# ModelP_ytki.net
KiCad netlist of a schematic drawn in EAGLE
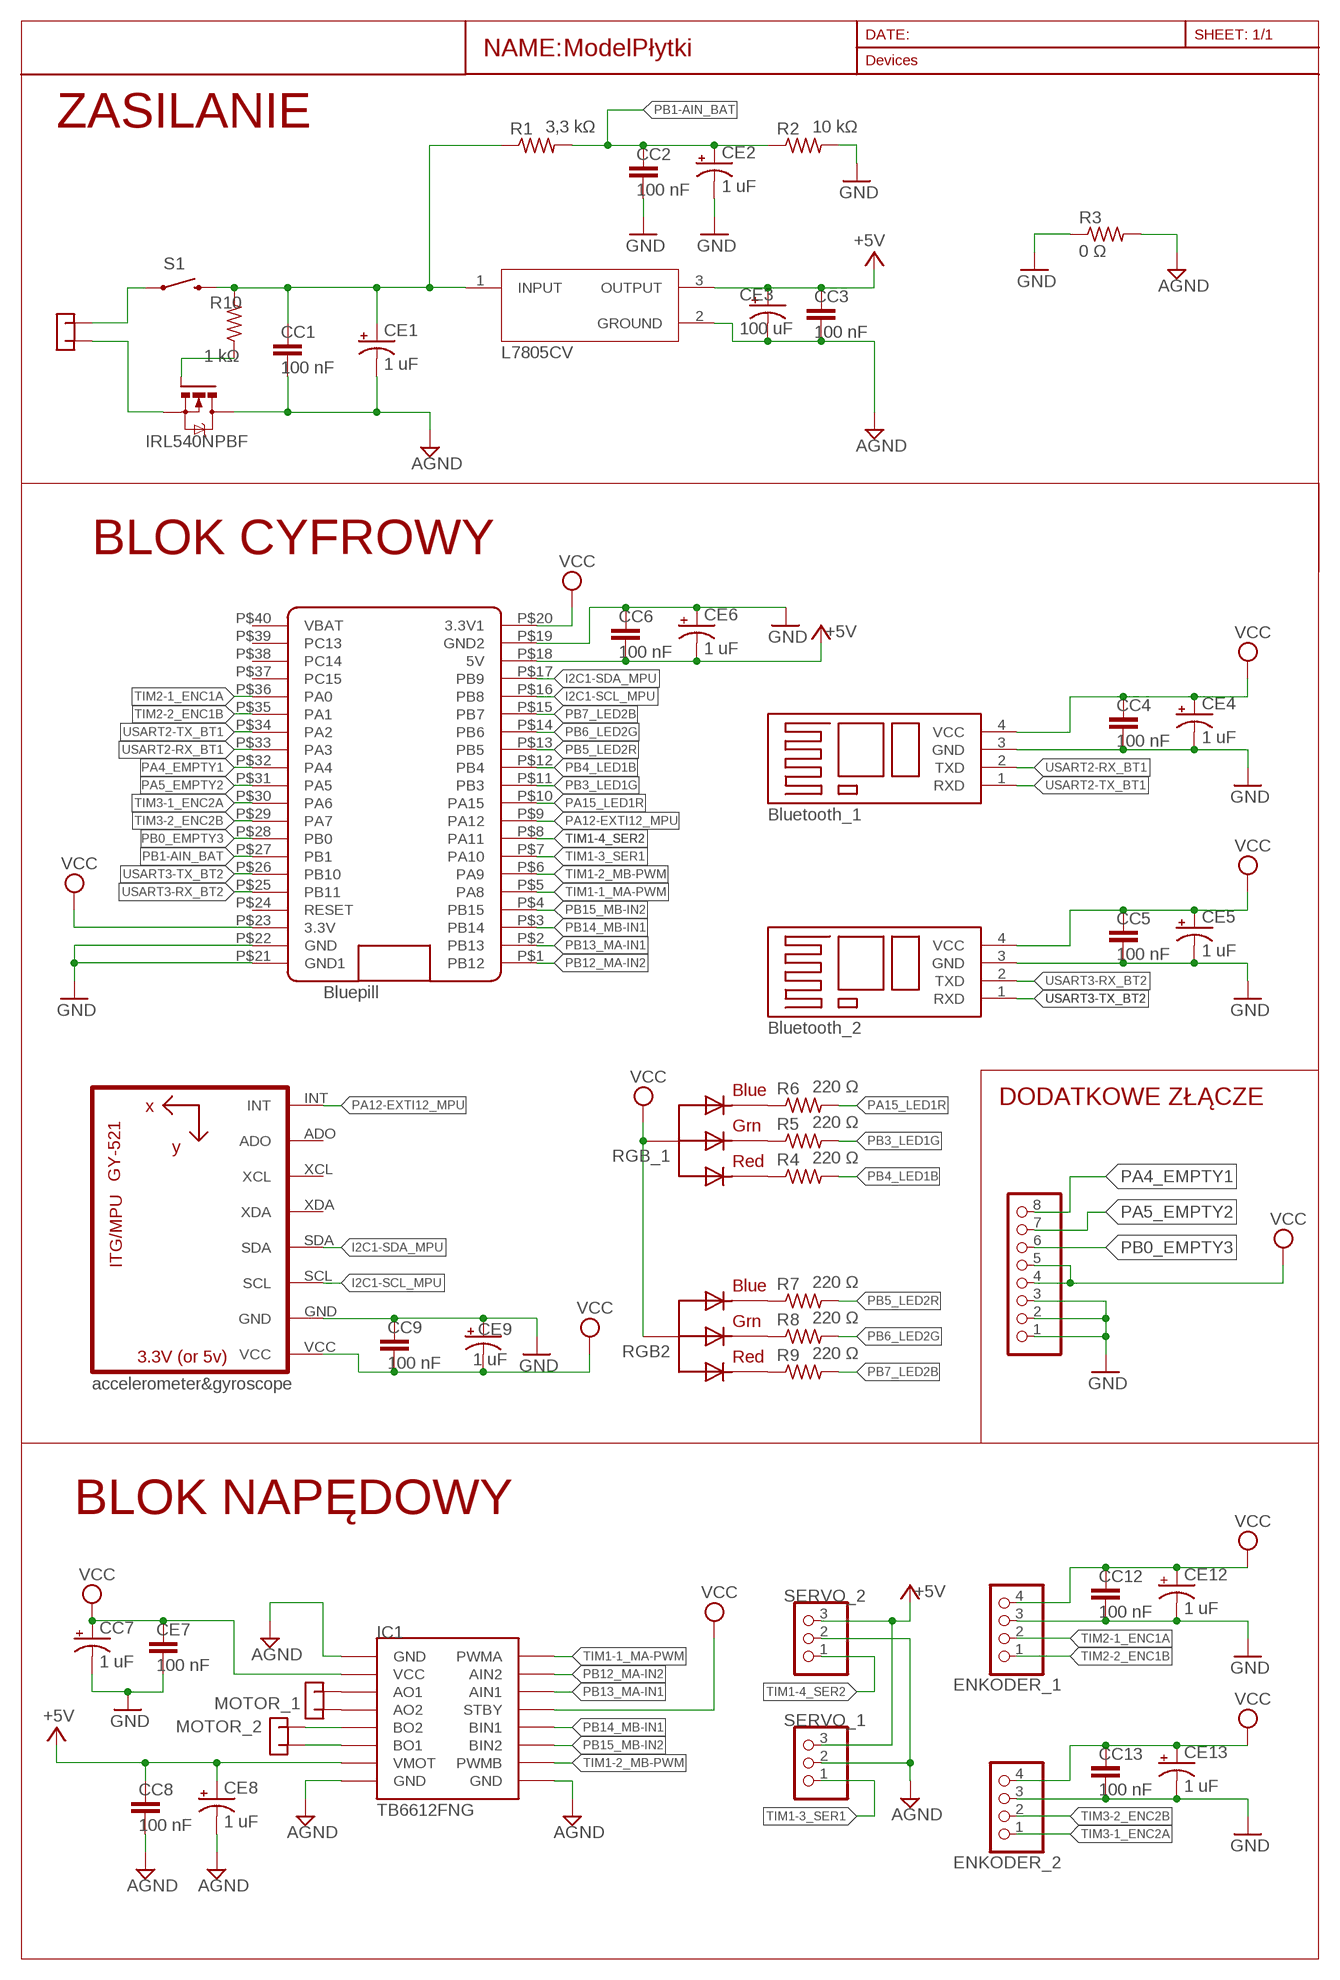
[diagram p0: schematic, sheet 1]

(export (version "E")
  (design (tool "Eeschema 10.0.6"))
  (components
    (comp (ref "BATERIA")
      (value "-CON2")
      (footprint "eagle-import:CON2")
      (libsource (lib "eagle-import") (part "my_tango_-CON2"))
    )
    (comp (ref "BLUETOOTH2")
      (value "BLUETOOTH")
      (footprint "eagle-import:BLUETOOTH")
      (libsource (lib "eagle-import") (part "BLUETOOTH"))
    )
    (comp (ref "BLUETOOTH3")
      (value "BLUETOOTH")
      (footprint "eagle-import:BLUETOOTH")
      (libsource (lib "eagle-import") (part "BLUETOOTH"))
    )
    (comp (ref "CC1")
      (value "100 nF")
      (footprint "eagle-import:C025-030X050")
      (libsource (lib "eagle-import") (part "C-EU025-030X050"))
    )
    (comp (ref "CC2")
      (value "100 nF")
      (footprint "eagle-import:C025-030X050")
      (libsource (lib "eagle-import") (part "C-EU025-030X050"))
    )
    (comp (ref "CC3")
      (value "100 nF")
      (footprint "eagle-import:C025-030X050")
      (libsource (lib "eagle-import") (part "C-EU025-030X050"))
    )
    (comp (ref "CC4")
      (value "100 nF")
      (footprint "eagle-import:C025-030X050")
      (libsource (lib "eagle-import") (part "C-EU025-030X050"))
    )
    (comp (ref "CC5")
      (value "100 nF")
      (footprint "eagle-import:C025-030X050")
      (libsource (lib "eagle-import") (part "C-EU025-030X050"))
    )
    (comp (ref "CC6")
      (value "100 nF")
      (footprint "eagle-import:C025-030X050")
      (libsource (lib "eagle-import") (part "C-EU025-030X050"))
    )
    (comp (ref "CC7")
      (value "1 uF")
      (footprint "eagle-import:TT2D5")
      (libsource (lib "eagle-import") (part "CPOL-USTT2D5"))
    )
    (comp (ref "CC8")
      (value "100 nF")
      (footprint "eagle-import:C025-030X050")
      (libsource (lib "eagle-import") (part "C-EU025-030X050"))
    )
    (comp (ref "CC9")
      (value "100 nF")
      (footprint "eagle-import:C025-030X050")
      (libsource (lib "eagle-import") (part "C-EU025-030X050"))
    )
    (comp (ref "CC12")
      (value "100 nF")
      (footprint "eagle-import:C025-030X050")
      (libsource (lib "eagle-import") (part "C-EU025-030X050"))
    )
    (comp (ref "CC13")
      (value "100 nF")
      (footprint "eagle-import:C025-030X050")
      (libsource (lib "eagle-import") (part "C-EU025-030X050"))
    )
    (comp (ref "CE1")
      (value "1 uF")
      (footprint "eagle-import:TT2D5")
      (libsource (lib "eagle-import") (part "CPOL-USTT2D5"))
    )
    (comp (ref "CE2")
      (value "1 uF")
      (footprint "eagle-import:TT2D5")
      (libsource (lib "eagle-import") (part "CPOL-USTT2D5"))
    )
    (comp (ref "CE3")
      (value "100 uF")
      (footprint "eagle-import:TT2D5")
      (libsource (lib "eagle-import") (part "CPOL-USTT2D5"))
    )
    (comp (ref "CE4")
      (value "1 uF")
      (footprint "eagle-import:TT2D5")
      (libsource (lib "eagle-import") (part "CPOL-USTT2D5"))
    )
    (comp (ref "CE5")
      (value "1 uF")
      (footprint "eagle-import:TT2D5")
      (libsource (lib "eagle-import") (part "CPOL-USTT2D5"))
    )
    (comp (ref "CE6")
      (value "1 uF")
      (footprint "eagle-import:TT2D5")
      (libsource (lib "eagle-import") (part "CPOL-USTT2D5"))
    )
    (comp (ref "CE7")
      (value "100 nF")
      (footprint "eagle-import:C025-030X050")
      (libsource (lib "eagle-import") (part "C-EU025-030X050"))
    )
    (comp (ref "CE8")
      (value "1 uF")
      (footprint "eagle-import:TT2D5")
      (libsource (lib "eagle-import") (part "CPOL-USTT2D5"))
    )
    (comp (ref "CE9")
      (value "1 uF")
      (footprint "eagle-import:TT2D5")
      (libsource (lib "eagle-import") (part "CPOL-USTT2D5"))
    )
    (comp (ref "CE12")
      (value "1 uF")
      (footprint "eagle-import:TT2D5")
      (libsource (lib "eagle-import") (part "CPOL-USTT2D5"))
    )
    (comp (ref "CE13")
      (value "1 uF")
      (footprint "eagle-import:TT2D5")
      (libsource (lib "eagle-import") (part "CPOL-USTT2D5"))
    )
    (comp (ref "ENKODER_1")
      (value "PINHD-1X4")
      (footprint "eagle-import:1X04")
      (libsource (lib "eagle-import") (part "PINHD-1X4"))
    )
    (comp (ref "ENKODER_2")
      (value "PINHD-1X4")
      (footprint "eagle-import:1X04")
      (libsource (lib "eagle-import") (part "PINHD-1X4"))
    )
    (comp (ref "IC1")
      (value "MODUL_POLOLU")
      (footprint "eagle-import:MODUL_POLOLU")
      (libsource (lib "eagle-import") (part "MODUL_POLOLU"))
    )
    (comp (ref "IRL540NPBF")
      (value "IRF520")
      (footprint "eagle-import:TO220BV")
      (libsource (lib "eagle-import") (part "IRF520"))
    )
    (comp (ref "JP4")
      (value "PINHD-1X8BIG")
      (footprint "eagle-import:1X08-BIG")
      (libsource (lib "eagle-import") (part "PINHD-1X8BIG"))
    )
    (comp (ref "MOTOR_1")
      (value "-CON2")
      (footprint "eagle-import:CON2")
      (libsource (lib "eagle-import") (part "-CON2"))
    )
    (comp (ref "MOTOR_2")
      (value "-CON2")
      (footprint "eagle-import:CON2")
      (libsource (lib "eagle-import") (part "-CON2"))
    )
    (comp (ref "R1")
      (value "3,3 kΩ")
      (footprint "eagle-import:0309_12")
      (libsource (lib "eagle-import") (part "R-US_0309/12"))
    )
    (comp (ref "R2")
      (value "10 kΩ")
      (footprint "eagle-import:0309_12")
      (libsource (lib "eagle-import") (part "R-US_0309/12"))
    )
    (comp (ref "R3")
      (value "0 Ω")
      (footprint "eagle-import:0309_12")
      (libsource (lib "eagle-import") (part "R-US_0309/12"))
    )
    (comp (ref "R4")
      (value "220 Ω")
      (footprint "eagle-import:0309_12")
      (libsource (lib "eagle-import") (part "R-US_0309/12"))
    )
    (comp (ref "R5")
      (value "220 Ω")
      (footprint "eagle-import:0309_12")
      (libsource (lib "eagle-import") (part "R-US_0309/12"))
    )
    (comp (ref "R6")
      (value "220 Ω")
      (footprint "eagle-import:0309_12")
      (libsource (lib "eagle-import") (part "R-US_0309/12"))
    )
    (comp (ref "R7")
      (value "220 Ω")
      (footprint "eagle-import:0309_12")
      (libsource (lib "eagle-import") (part "R-US_0309/12"))
    )
    (comp (ref "R8")
      (value "220 Ω")
      (footprint "eagle-import:0309_12")
      (libsource (lib "eagle-import") (part "R-US_0309/12"))
    )
    (comp (ref "R9")
      (value "220 Ω")
      (footprint "eagle-import:0309_12")
      (libsource (lib "eagle-import") (part "R-US_0309/12"))
    )
    (comp (ref "R10")
      (value "1 kΩ")
      (footprint "eagle-import:0309_12")
      (libsource (lib "eagle-import") (part "R-US_0309/12"))
    )
    (comp (ref "RGB2")
      (value "RGBLED_CA-5MM")
      (footprint "eagle-import:LED5MMRGB")
      (libsource (lib "eagle-import") (part "RGBLED_CA-5MM"))
    )
    (comp (ref "RGB_1")
      (value "RGBLED_CA-5MM")
      (footprint "eagle-import:LED5MMRGB")
      (libsource (lib "eagle-import") (part "RGBLED_CA-5MM"))
    )
    (comp (ref "S1")
      (value "RS032G05A3SM-SPST-MOMENTARY-SWSMD-1101NE")
      (footprint "eagle-import:TACTILE-SWITCH-1101NE")
      (libsource (lib "eagle-import") (part "RS032G05A3SM-SPST-MOMENTARY-SWSMD-1101NE"))
    )
    (comp (ref "SERVO_1")
      (value "PINHD-1X3")
      (footprint "eagle-import:1X03")
      (libsource (lib "eagle-import") (part "PINHD-1X3"))
    )
    (comp (ref "SERVO_2")
      (value "PINHD-1X3")
      (footprint "eagle-import:1X03")
      (libsource (lib "eagle-import") (part "PINHD-1X3"))
    )
    (comp (ref "U$2")
      (value "BLUE_PILL")
      (footprint "eagle-import:BLUE_PILL")
      (libsource (lib "eagle-import") (part "BLUE_PILL"))
    )
    (comp (ref "U2")
      (value "L7805CV")
      (footprint "eagle-import:TO255P1040X460X1968-3")
      (fields (field (name "MF") "STMicroelectronics"))
      (libsource (lib "eagle-import") (part "L7805CV"))
    )
    (comp (ref "U4")
      (value "GY-521MPU6050")
      (footprint "eagle-import:GY-521")
      (libsource (lib "eagle-import") (part "GY-521MPU6050"))
    )
  )
  (nets
    (net (code "1") (name "+5V") (class "Default")
      (node (ref "CC3") (pin "1") (pinfunction "1_1") (pintype "passive"))
      (node (ref "CC6") (pin "2") (pinfunction "2_2") (pintype "passive"))
      (node (ref "CC8") (pin "1") (pinfunction "1_1") (pintype "passive"))
      (node (ref "CE3") (pin "+") (pinfunction "+_+") (pintype "passive"))
      (node (ref "CE6") (pin "-") (pinfunction "-_-") (pintype "passive"))
      (node (ref "CE8") (pin "+") (pinfunction "+_+") (pintype "passive"))
      (node (ref "IC1") (pin "VMOT") (pinfunction "VMOT_VMOT") (pintype "bidirectional"))
      (node (ref "SERVO_1") (pin "3") (pinfunction "3_3") (pintype "passive"))
      (node (ref "SERVO_2") (pin "3") (pinfunction "3_3") (pintype "passive"))
      (node (ref "U$2") (pin "P$18") (pinfunction "5V_P$18") (pintype "bidirectional"))
      (node (ref "U2") (pin "3") (pinfunction "OUTPUT_3") (pintype "output"))
    )
    (net (code "2") (name "AGND") (class "Default")
      (node (ref "CC1") (pin "2") (pinfunction "2_2") (pintype "passive"))
      (node (ref "CC3") (pin "2") (pinfunction "2_2") (pintype "passive"))
      (node (ref "CC8") (pin "2") (pinfunction "2_2") (pintype "passive"))
      (node (ref "CE1") (pin "-") (pinfunction "-_-") (pintype "passive"))
      (node (ref "CE3") (pin "-") (pinfunction "-_-") (pintype "passive"))
      (node (ref "CE8") (pin "-") (pinfunction "-_-") (pintype "passive"))
      (node (ref "IC1") (pin "GND1") (pinfunction "GND_GND1") (pintype "bidirectional"))
      (node (ref "IC1") (pin "GND2") (pinfunction "GND_GND2") (pintype "bidirectional"))
      (node (ref "IC1") (pin "GND3") (pinfunction "GND_GND3") (pintype "bidirectional"))
      (node (ref "IRL540NPBF") (pin "D") (pinfunction "D_D") (pintype "passive"))
      (node (ref "R3") (pin "2") (pinfunction "2_2") (pintype "passive"))
      (node (ref "SERVO_1") (pin "2") (pinfunction "2_2") (pintype "passive"))
      (node (ref "SERVO_2") (pin "2") (pinfunction "2_2") (pintype "passive"))
      (node (ref "U2") (pin "2") (pinfunction "GROUND_2") (pintype "power_in"))
    )
    (net (code "3") (name "GND") (class "Default")
      (node (ref "BLUETOOTH2") (pin "3") (pinfunction "GND_3") (pintype "power_in"))
      (node (ref "BLUETOOTH3") (pin "3") (pinfunction "GND_3") (pintype "power_in"))
      (node (ref "CC12") (pin "2") (pinfunction "2_2") (pintype "passive"))
      (node (ref "CC13") (pin "2") (pinfunction "2_2") (pintype "passive"))
      (node (ref "CC2") (pin "2") (pinfunction "2_2") (pintype "passive"))
      (node (ref "CC4") (pin "2") (pinfunction "2_2") (pintype "passive"))
      (node (ref "CC5") (pin "2") (pinfunction "2_2") (pintype "passive"))
      (node (ref "CC6") (pin "1") (pinfunction "1_1") (pintype "passive"))
      (node (ref "CC7") (pin "-") (pinfunction "-_-") (pintype "passive"))
      (node (ref "CC9") (pin "1") (pinfunction "1_1") (pintype "passive"))
      (node (ref "CE12") (pin "-") (pinfunction "-_-") (pintype "passive"))
      (node (ref "CE13") (pin "-") (pinfunction "-_-") (pintype "passive"))
      (node (ref "CE2") (pin "-") (pinfunction "-_-") (pintype "passive"))
      (node (ref "CE4") (pin "-") (pinfunction "-_-") (pintype "passive"))
      (node (ref "CE5") (pin "-") (pinfunction "-_-") (pintype "passive"))
      (node (ref "CE6") (pin "+") (pinfunction "+_+") (pintype "passive"))
      (node (ref "CE7") (pin "2") (pinfunction "2_2") (pintype "passive"))
      (node (ref "CE9") (pin "+") (pinfunction "+_+") (pintype "passive"))
      (node (ref "ENKODER_1") (pin "3") (pinfunction "3_3") (pintype "passive"))
      (node (ref "ENKODER_2") (pin "3") (pinfunction "3_3") (pintype "passive"))
      (node (ref "JP4") (pin "1") (pinfunction "1_1") (pintype "passive"))
      (node (ref "JP4") (pin "2") (pinfunction "2_2") (pintype "passive"))
      (node (ref "JP4") (pin "3") (pinfunction "3_3") (pintype "passive"))
      (node (ref "R2") (pin "2") (pinfunction "2_2") (pintype "passive"))
      (node (ref "R3") (pin "1") (pinfunction "1_1") (pintype "passive"))
      (node (ref "U$2") (pin "P$19") (pinfunction "GND2_P$19") (pintype "bidirectional"))
      (node (ref "U$2") (pin "P$21") (pinfunction "GND1_P$21") (pintype "power_in"))
      (node (ref "U$2") (pin "P$22") (pinfunction "GND_P$22") (pintype "bidirectional"))
      (node (ref "U4") (pin "GND") (pinfunction "GND_GND") (pintype "bidirectional"))
    )
    (net (code "4") (name "I2C1-SCL_MPU") (class "Default")
      (node (ref "U$2") (pin "P$16") (pinfunction "PB8_P$16") (pintype "bidirectional"))
      (node (ref "U4") (pin "SCL") (pinfunction "SCL_SCL") (pintype "bidirectional"))
    )
    (net (code "5") (name "I2C1-SDA_MPU") (class "Default")
      (node (ref "U$2") (pin "P$17") (pinfunction "PB9_P$17") (pintype "bidirectional"))
      (node (ref "U4") (pin "SDA") (pinfunction "SDA_SDA") (pintype "bidirectional"))
    )
    (net (code "6") (name "Net-(BATERIA-1)") (class "Default")
      (node (ref "BATERIA") (pin "P$1") (pinfunction "1_P$1") (pintype "passive"))
      (node (ref "S1") (pin "1") (pinfunction "1_1") (pintype "passive"))
    )
    (net (code "7") (name "Net-(BATERIA-2)") (class "Default")
      (node (ref "BATERIA") (pin "P$2") (pinfunction "2_P$2") (pintype "passive"))
      (node (ref "IRL540NPBF") (pin "S") (pinfunction "S_S") (pintype "passive"))
    )
    (net (code "8") (name "Net-(IC1-AO2)") (class "Default")
      (node (ref "IC1") (pin "A02") (pinfunction "AO2_A02") (pintype "bidirectional"))
      (node (ref "MOTOR_1") (pin "P$2") (pinfunction "2_P$2") (pintype "passive"))
    )
    (net (code "9") (name "Net-(IRL540NPBF-PadG)") (class "Default")
      (node (ref "IRL540NPBF") (pin "G") (pinfunction "G_G") (pintype "passive"))
      (node (ref "R10") (pin "1") (pinfunction "1_1") (pintype "passive"))
    )
    (net (code "10") (name "Net-(MOTOR_1-1)") (class "Default")
      (node (ref "IC1") (pin "AO1") (pinfunction "AO1_AO1") (pintype "bidirectional"))
      (node (ref "MOTOR_1") (pin "P$1") (pinfunction "1_P$1") (pintype "passive"))
    )
    (net (code "11") (name "Net-(MOTOR_2-1)") (class "Default")
      (node (ref "IC1") (pin "BO2") (pinfunction "BO2_BO2") (pintype "bidirectional"))
      (node (ref "MOTOR_2") (pin "P$1") (pinfunction "1_P$1") (pintype "passive"))
    )
    (net (code "12") (name "Net-(MOTOR_2-2)") (class "Default")
      (node (ref "IC1") (pin "BO1") (pinfunction "BO1_BO1") (pintype "bidirectional"))
      (node (ref "MOTOR_2") (pin "P$2") (pinfunction "2_P$2") (pintype "passive"))
    )
    (net (code "13") (name "Net-(RGB2-BLUE)") (class "Default")
      (node (ref "R7") (pin "1") (pinfunction "1_1") (pintype "passive"))
      (node (ref "RGB2") (pin "4") (pinfunction "BLUE_4") (pintype "bidirectional"))
    )
    (net (code "14") (name "Net-(RGB2-GREEN)") (class "Default")
      (node (ref "R8") (pin "1") (pinfunction "1_1") (pintype "passive"))
      (node (ref "RGB2") (pin "3") (pinfunction "GREEN_3") (pintype "bidirectional"))
    )
    (net (code "15") (name "Net-(RGB2-RED)") (class "Default")
      (node (ref "R9") (pin "1") (pinfunction "1_1") (pintype "passive"))
      (node (ref "RGB2") (pin "1") (pinfunction "RED_1") (pintype "bidirectional"))
    )
    (net (code "16") (name "Net-(RGB_1-BLUE)") (class "Default")
      (node (ref "R6") (pin "1") (pinfunction "1_1") (pintype "passive"))
      (node (ref "RGB_1") (pin "4") (pinfunction "BLUE_4") (pintype "bidirectional"))
    )
    (net (code "17") (name "Net-(RGB_1-GREEN)") (class "Default")
      (node (ref "R5") (pin "1") (pinfunction "1_1") (pintype "passive"))
      (node (ref "RGB_1") (pin "3") (pinfunction "GREEN_3") (pintype "bidirectional"))
    )
    (net (code "18") (name "Net-(RGB_1-RED)") (class "Default")
      (node (ref "R4") (pin "1") (pinfunction "1_1") (pintype "passive"))
      (node (ref "RGB_1") (pin "1") (pinfunction "RED_1") (pintype "bidirectional"))
    )
    (net (code "19") (name "Net-(U2-INPUT)") (class "Default")
      (node (ref "CC1") (pin "1") (pinfunction "1_1") (pintype "passive"))
      (node (ref "CE1") (pin "+") (pinfunction "+_+") (pintype "passive"))
      (node (ref "R1") (pin "1") (pinfunction "1_1") (pintype "passive"))
      (node (ref "R10") (pin "2") (pinfunction "2_2") (pintype "passive"))
      (node (ref "S1") (pin "2") (pinfunction "2_2") (pintype "passive"))
      (node (ref "U2") (pin "1") (pinfunction "INPUT_1") (pintype "input"))
    )
    (net (code "20") (name "PA4_EMPTY1") (class "Default")
      (node (ref "JP4") (pin "8") (pinfunction "8_8") (pintype "passive"))
      (node (ref "U$2") (pin "P$32") (pinfunction "PA4_P$32") (pintype "bidirectional"))
    )
    (net (code "21") (name "PA5_EMPTY2") (class "Default")
      (node (ref "JP4") (pin "7") (pinfunction "7_7") (pintype "passive"))
      (node (ref "U$2") (pin "P$31") (pinfunction "PA5_P$31") (pintype "bidirectional"))
    )
    (net (code "22") (name "PA12-EXTI12_MPU") (class "Default")
      (node (ref "U$2") (pin "P$9") (pinfunction "PA12_P$9") (pintype "bidirectional"))
      (node (ref "U4") (pin "INT") (pinfunction "INT_INT") (pintype "bidirectional"))
    )
    (net (code "23") (name "PA15_LED1R") (class "Default")
      (node (ref "R6") (pin "2") (pinfunction "2_2") (pintype "passive"))
      (node (ref "U$2") (pin "P$10") (pinfunction "PA15_P$10") (pintype "bidirectional"))
    )
    (net (code "24") (name "PB0_EMPTY3") (class "Default")
      (node (ref "JP4") (pin "6") (pinfunction "6_6") (pintype "passive"))
      (node (ref "U$2") (pin "P$28") (pinfunction "PB0_P$28") (pintype "bidirectional"))
    )
    (net (code "25") (name "PB1-AIN_BAT") (class "Default")
      (node (ref "CC2") (pin "1") (pinfunction "1_1") (pintype "passive"))
      (node (ref "CE2") (pin "+") (pinfunction "+_+") (pintype "passive"))
      (node (ref "R1") (pin "2") (pinfunction "2_2") (pintype "passive"))
      (node (ref "R2") (pin "1") (pinfunction "1_1") (pintype "passive"))
      (node (ref "U$2") (pin "P$27") (pinfunction "PB1_P$27") (pintype "bidirectional"))
    )
    (net (code "26") (name "PB3_LED1G") (class "Default")
      (node (ref "R5") (pin "2") (pinfunction "2_2") (pintype "passive"))
      (node (ref "U$2") (pin "P$11") (pinfunction "PB3_P$11") (pintype "bidirectional"))
    )
    (net (code "27") (name "PB4_LED1B") (class "Default")
      (node (ref "R4") (pin "2") (pinfunction "2_2") (pintype "passive"))
      (node (ref "U$2") (pin "P$12") (pinfunction "PB4_P$12") (pintype "bidirectional"))
    )
    (net (code "28") (name "PB5_LED2R") (class "Default")
      (node (ref "R7") (pin "2") (pinfunction "2_2") (pintype "passive"))
      (node (ref "U$2") (pin "P$13") (pinfunction "PB5_P$13") (pintype "bidirectional"))
    )
    (net (code "29") (name "PB6_LED2G") (class "Default")
      (node (ref "R8") (pin "2") (pinfunction "2_2") (pintype "passive"))
      (node (ref "U$2") (pin "P$14") (pinfunction "PB6_P$14") (pintype "bidirectional"))
    )
    (net (code "30") (name "PB7_LED2B") (class "Default")
      (node (ref "R9") (pin "2") (pinfunction "2_2") (pintype "passive"))
      (node (ref "U$2") (pin "P$15") (pinfunction "PB7_P$15") (pintype "bidirectional"))
    )
    (net (code "31") (name "PB12_MA-IN2") (class "Default")
      (node (ref "IC1") (pin "AIN2") (pinfunction "AIN2_AIN2") (pintype "bidirectional"))
      (node (ref "U$2") (pin "P$1") (pinfunction "PB12_P$1") (pintype "bidirectional"))
    )
    (net (code "32") (name "PB13_MA-IN1") (class "Default")
      (node (ref "IC1") (pin "AIN1") (pinfunction "AIN1_AIN1") (pintype "bidirectional"))
      (node (ref "U$2") (pin "P$2") (pinfunction "PB13_P$2") (pintype "bidirectional"))
    )
    (net (code "33") (name "PB14_MB-IN1") (class "Default")
      (node (ref "IC1") (pin "BIN1") (pinfunction "BIN1_BIN1") (pintype "bidirectional"))
      (node (ref "U$2") (pin "P$3") (pinfunction "PB14_P$3") (pintype "bidirectional"))
    )
    (net (code "34") (name "PB15_MB-IN2") (class "Default")
      (node (ref "IC1") (pin "BIN2") (pinfunction "BIN2_BIN2") (pintype "bidirectional"))
      (node (ref "U$2") (pin "P$4") (pinfunction "PB15_P$4") (pintype "bidirectional"))
    )
    (net (code "35") (name "TIM1-1_MA-PWM") (class "Default")
      (node (ref "IC1") (pin "PWMA") (pinfunction "PWMA_PWMA") (pintype "bidirectional"))
      (node (ref "U$2") (pin "P$5") (pinfunction "PA8_P$5") (pintype "bidirectional"))
    )
    (net (code "36") (name "TIM1-2_MB-PWM") (class "Default")
      (node (ref "IC1") (pin "PWMB") (pinfunction "PWMB_PWMB") (pintype "bidirectional"))
      (node (ref "U$2") (pin "P$6") (pinfunction "PA9_P$6") (pintype "bidirectional"))
    )
    (net (code "37") (name "TIM1-3_SER1") (class "Default")
      (node (ref "SERVO_1") (pin "1") (pinfunction "1_1") (pintype "passive"))
      (node (ref "U$2") (pin "P$7") (pinfunction "PA10_P$7") (pintype "bidirectional"))
    )
    (net (code "38") (name "TIM1-4_SER2") (class "Default")
      (node (ref "SERVO_2") (pin "1") (pinfunction "1_1") (pintype "passive"))
      (node (ref "U$2") (pin "P$8") (pinfunction "PA11_P$8") (pintype "bidirectional"))
    )
    (net (code "39") (name "TIM2-1_ENC1A") (class "Default")
      (node (ref "ENKODER_1") (pin "2") (pinfunction "2_2") (pintype "passive"))
      (node (ref "U$2") (pin "P$36") (pinfunction "PA0_P$36") (pintype "bidirectional"))
    )
    (net (code "40") (name "TIM2-2_ENC1B") (class "Default")
      (node (ref "ENKODER_1") (pin "1") (pinfunction "1_1") (pintype "passive"))
      (node (ref "U$2") (pin "P$35") (pinfunction "PA1_P$35") (pintype "bidirectional"))
    )
    (net (code "41") (name "TIM3-1_ENC2A") (class "Default")
      (node (ref "ENKODER_2") (pin "1") (pinfunction "1_1") (pintype "passive"))
      (node (ref "U$2") (pin "P$30") (pinfunction "PA6_P$30") (pintype "bidirectional"))
    )
    (net (code "42") (name "TIM3-2_ENC2B") (class "Default")
      (node (ref "ENKODER_2") (pin "2") (pinfunction "2_2") (pintype "passive"))
      (node (ref "U$2") (pin "P$29") (pinfunction "PA7_P$29") (pintype "bidirectional"))
    )
    (net (code "43") (name "USART2-RX_BT1") (class "Default")
      (node (ref "BLUETOOTH2") (pin "2") (pinfunction "TXD_2") (pintype "bidirectional"))
      (node (ref "U$2") (pin "P$33") (pinfunction "PA3_P$33") (pintype "bidirectional"))
    )
    (net (code "44") (name "USART2-TX_BT1") (class "Default")
      (node (ref "BLUETOOTH2") (pin "1") (pinfunction "RXD_1") (pintype "bidirectional"))
      (node (ref "U$2") (pin "P$34") (pinfunction "PA2_P$34") (pintype "bidirectional"))
    )
    (net (code "45") (name "USART3-RX_BT2") (class "Default")
      (node (ref "BLUETOOTH3") (pin "2") (pinfunction "TXD_2") (pintype "bidirectional"))
      (node (ref "U$2") (pin "P$25") (pinfunction "PB11_P$25") (pintype "bidirectional"))
    )
    (net (code "46") (name "USART3-TX_BT2") (class "Default")
      (node (ref "BLUETOOTH3") (pin "1") (pinfunction "RXD_1") (pintype "bidirectional"))
      (node (ref "U$2") (pin "P$26") (pinfunction "PB10_P$26") (pintype "bidirectional"))
    )
    (net (code "47") (name "VCC") (class "Default")
      (node (ref "BLUETOOTH2") (pin "4") (pinfunction "VCC_4") (pintype "power_in"))
      (node (ref "BLUETOOTH3") (pin "4") (pinfunction "VCC_4") (pintype "power_in"))
      (node (ref "CC12") (pin "1") (pinfunction "1_1") (pintype "passive"))
      (node (ref "CC13") (pin "1") (pinfunction "1_1") (pintype "passive"))
      (node (ref "CC4") (pin "1") (pinfunction "1_1") (pintype "passive"))
      (node (ref "CC5") (pin "1") (pinfunction "1_1") (pintype "passive"))
      (node (ref "CC7") (pin "+") (pinfunction "+_+") (pintype "passive"))
      (node (ref "CC9") (pin "2") (pinfunction "2_2") (pintype "passive"))
      (node (ref "CE12") (pin "+") (pinfunction "+_+") (pintype "passive"))
      (node (ref "CE13") (pin "+") (pinfunction "+_+") (pintype "passive"))
      (node (ref "CE4") (pin "+") (pinfunction "+_+") (pintype "passive"))
      (node (ref "CE5") (pin "+") (pinfunction "+_+") (pintype "passive"))
      (node (ref "CE7") (pin "1") (pinfunction "1_1") (pintype "passive"))
      (node (ref "CE9") (pin "-") (pinfunction "-_-") (pintype "passive"))
      (node (ref "ENKODER_1") (pin "4") (pinfunction "4_4") (pintype "passive"))
      (node (ref "ENKODER_2") (pin "4") (pinfunction "4_4") (pintype "passive"))
      (node (ref "IC1") (pin "STBY") (pinfunction "STBY_STBY") (pintype "bidirectional"))
      (node (ref "IC1") (pin "VCC") (pinfunction "VCC_VCC") (pintype "bidirectional"))
      (node (ref "JP4") (pin "4") (pinfunction "4_4") (pintype "passive"))
      (node (ref "JP4") (pin "5") (pinfunction "5_5") (pintype "passive"))
      (node (ref "RGB2") (pin "2") (pinfunction "VCC_2") (pintype "bidirectional"))
      (node (ref "RGB_1") (pin "2") (pinfunction "VCC_2") (pintype "bidirectional"))
      (node (ref "U$2") (pin "P$20") (pinfunction "3.3V1_P$20") (pintype "bidirectional"))
      (node (ref "U$2") (pin "P$23") (pinfunction "3.3V_P$23") (pintype "bidirectional"))
      (node (ref "U4") (pin "VCC") (pinfunction "VCC_VCC") (pintype "bidirectional"))
    )
    (net (code "48") (name "unconnected-(U$2-PC13-PadP$39)") (class "Default")
      (node (ref "U$2") (pin "P$39") (pinfunction "PC13_P$39") (pintype "bidirectional"))
    )
    (net (code "49") (name "unconnected-(U$2-PC14-PadP$38)") (class "Default")
      (node (ref "U$2") (pin "P$38") (pinfunction "PC14_P$38") (pintype "bidirectional"))
    )
    (net (code "50") (name "unconnected-(U$2-PC15-PadP$37)") (class "Default")
      (node (ref "U$2") (pin "P$37") (pinfunction "PC15_P$37") (pintype "bidirectional"))
    )
    (net (code "51") (name "unconnected-(U$2-RESET-PadP$24)") (class "Default")
      (node (ref "U$2") (pin "P$24") (pinfunction "RESET_P$24") (pintype "bidirectional"))
    )
    (net (code "52") (name "unconnected-(U$2-VBAT-PadP$40)") (class "Default")
      (node (ref "U$2") (pin "P$40") (pinfunction "VBAT_P$40") (pintype "bidirectional"))
    )
    (net (code "53") (name "unconnected-(U4-PadADO)") (class "Default")
      (node (ref "U4") (pin "ADO") (pinfunction "ADO_ADO") (pintype "bidirectional"))
    )
    (net (code "54") (name "unconnected-(U4-PadXCL)") (class "Default")
      (node (ref "U4") (pin "XCL") (pinfunction "XCL_XCL") (pintype "bidirectional"))
    )
    (net (code "55") (name "unconnected-(U4-PadXDA)") (class "Default")
      (node (ref "U4") (pin "XDA") (pinfunction "XDA_XDA") (pintype "bidirectional"))
    )
  )
)
